# B130.net
KiCad netlist of a schematic drawn in EAGLE
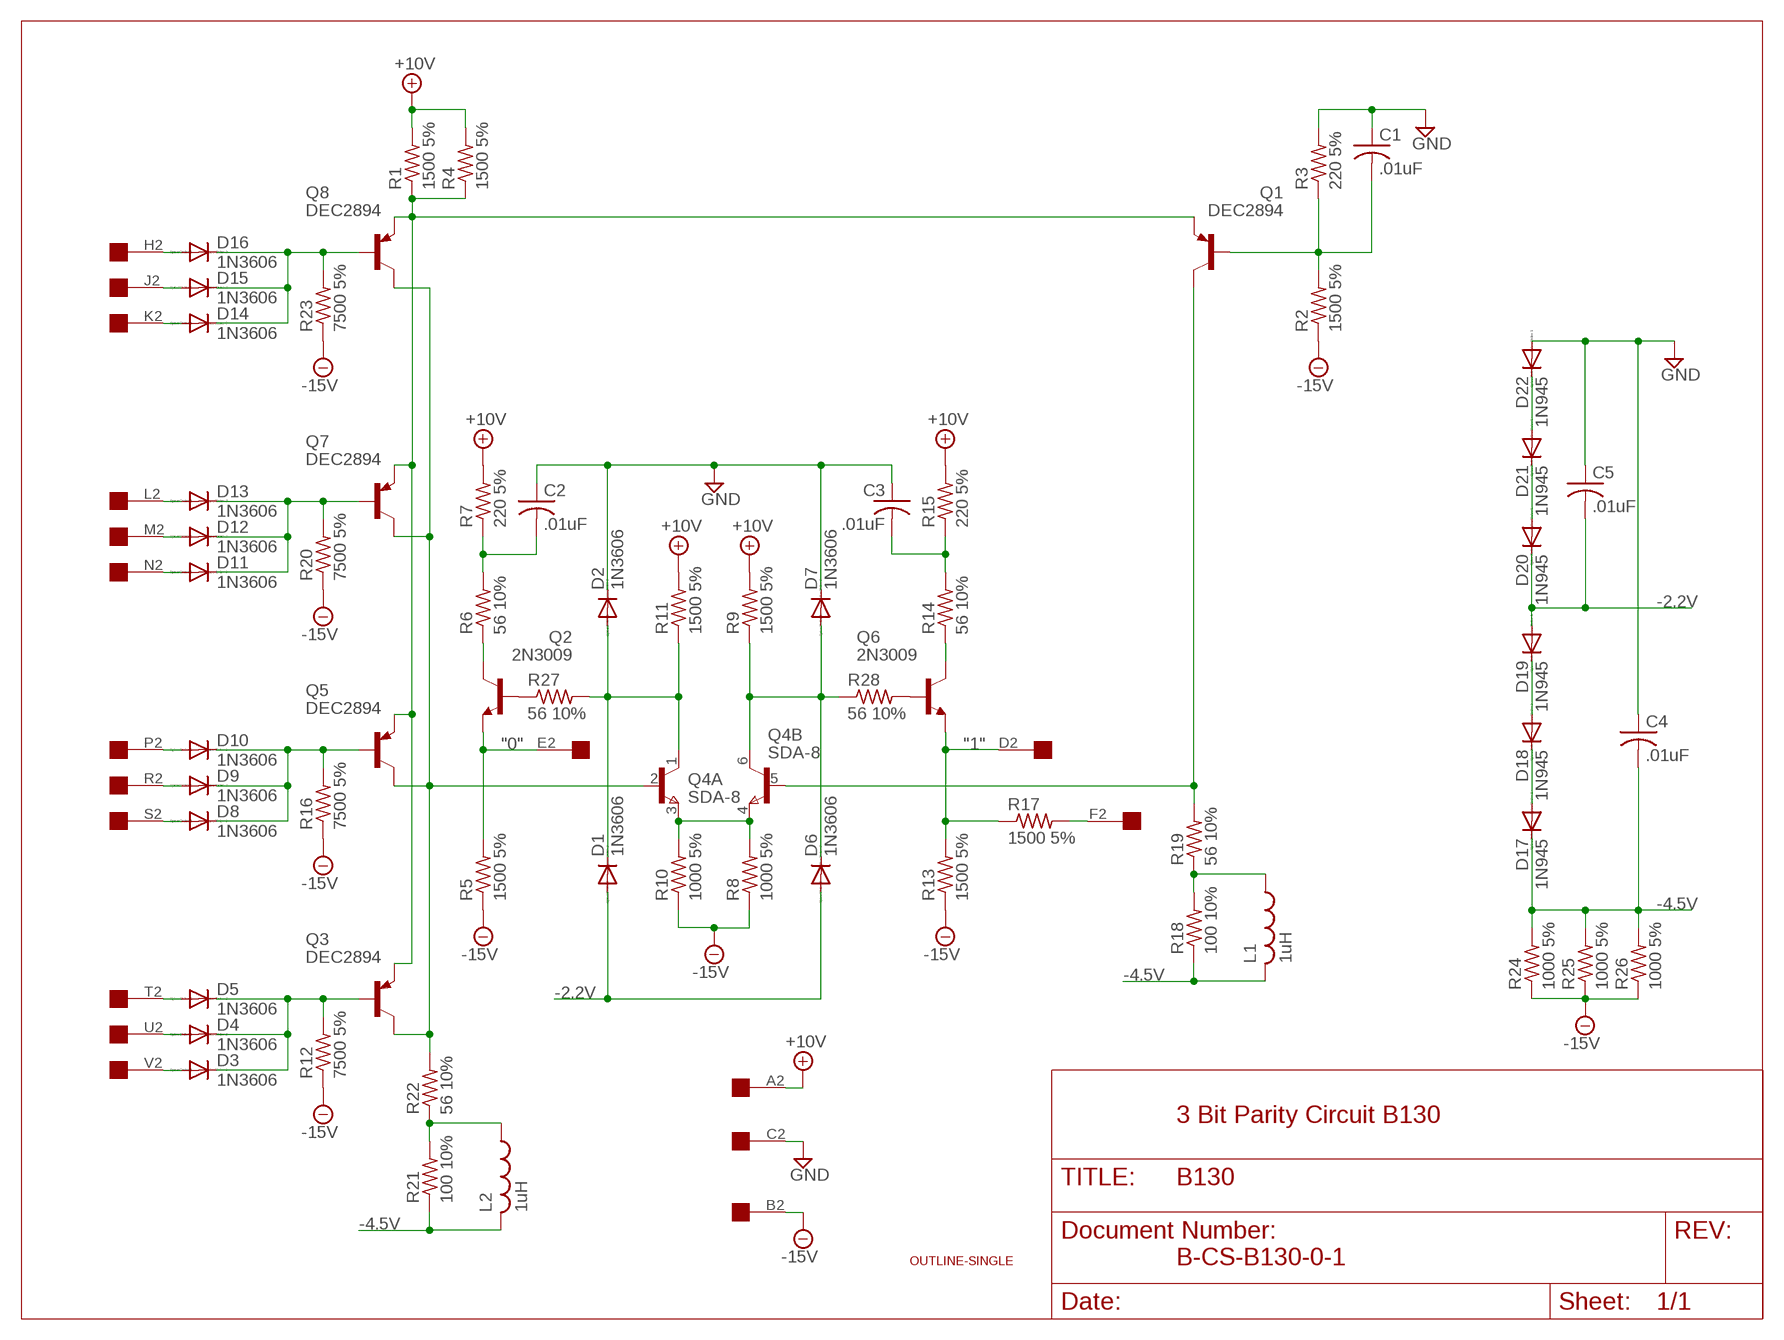
[diagram p0: schematic, sheet 1]

(export (version "E")
  (design (tool "Eeschema 10.0.6"))
  (components
    (comp (ref "C1")
      (value ".01uF")
      (footprint "eagle-import:C050-025X075")
      (libsource (lib "eagle-import") (part "C-US050-025X075"))
    )
    (comp (ref "C2")
      (value ".01uF")
      (footprint "eagle-import:C050-025X075")
      (libsource (lib "eagle-import") (part "C-US050-025X075"))
    )
    (comp (ref "C3")
      (value ".01uF")
      (footprint "eagle-import:C050-025X075")
      (libsource (lib "eagle-import") (part "C-US050-025X075"))
    )
    (comp (ref "C4")
      (value ".01uF")
      (footprint "eagle-import:C050-025X075")
      (libsource (lib "eagle-import") (part "C-US050-025X075"))
    )
    (comp (ref "C5")
      (value ".01uF")
      (footprint "eagle-import:C050-025X075")
      (libsource (lib "eagle-import") (part "C-US050-025X075"))
    )
    (comp (ref "D1")
      (value "1N3606")
      (footprint "eagle-import:DO35-10")
      (libsource (lib "eagle-import") (part "1N4148DO35-10"))
    )
    (comp (ref "D2")
      (value "1N3606")
      (footprint "eagle-import:DO35-10")
      (libsource (lib "eagle-import") (part "1N4148DO35-10"))
    )
    (comp (ref "D3")
      (value "1N3606")
      (footprint "eagle-import:DO35-10")
      (libsource (lib "eagle-import") (part "1N4148DO35-10"))
    )
    (comp (ref "D4")
      (value "1N3606")
      (footprint "eagle-import:DO35-10")
      (libsource (lib "eagle-import") (part "1N4148DO35-10"))
    )
    (comp (ref "D5")
      (value "1N3606")
      (footprint "eagle-import:DO35-10")
      (libsource (lib "eagle-import") (part "1N4148DO35-10"))
    )
    (comp (ref "D6")
      (value "1N3606")
      (footprint "eagle-import:DO35-10")
      (libsource (lib "eagle-import") (part "1N4148DO35-10"))
    )
    (comp (ref "D7")
      (value "1N3606")
      (footprint "eagle-import:DO35-10")
      (libsource (lib "eagle-import") (part "1N4148DO35-10"))
    )
    (comp (ref "D8")
      (value "1N3606")
      (footprint "eagle-import:DO35-10")
      (libsource (lib "eagle-import") (part "1N4148DO35-10"))
    )
    (comp (ref "D9")
      (value "1N3606")
      (footprint "eagle-import:DO35-10")
      (libsource (lib "eagle-import") (part "1N4148DO35-10"))
    )
    (comp (ref "D10")
      (value "1N3606")
      (footprint "eagle-import:DO35-10")
      (libsource (lib "eagle-import") (part "1N4148DO35-10"))
    )
    (comp (ref "D11")
      (value "1N3606")
      (footprint "eagle-import:DO35-10")
      (libsource (lib "eagle-import") (part "1N4148DO35-10"))
    )
    (comp (ref "D12")
      (value "1N3606")
      (footprint "eagle-import:DO35-10")
      (libsource (lib "eagle-import") (part "1N4148DO35-10"))
    )
    (comp (ref "D13")
      (value "1N3606")
      (footprint "eagle-import:DO35-10")
      (libsource (lib "eagle-import") (part "1N4148DO35-10"))
    )
    (comp (ref "D14")
      (value "1N3606")
      (footprint "eagle-import:DO35-10")
      (libsource (lib "eagle-import") (part "1N4148DO35-10"))
    )
    (comp (ref "D15")
      (value "1N3606")
      (footprint "eagle-import:DO35-10")
      (libsource (lib "eagle-import") (part "1N4148DO35-10"))
    )
    (comp (ref "D16")
      (value "1N3606")
      (footprint "eagle-import:DO35-10")
      (libsource (lib "eagle-import") (part "1N4148DO35-10"))
    )
    (comp (ref "D17")
      (value "1N945")
      (footprint "eagle-import:DO35-10")
      (libsource (lib "eagle-import") (part "1N4148DO35-10"))
    )
    (comp (ref "D18")
      (value "1N945")
      (footprint "eagle-import:DO35-10")
      (libsource (lib "eagle-import") (part "1N4148DO35-10"))
    )
    (comp (ref "D19")
      (value "1N945")
      (footprint "eagle-import:DO35-10")
      (libsource (lib "eagle-import") (part "1N4148DO35-10"))
    )
    (comp (ref "D20")
      (value "1N945")
      (footprint "eagle-import:DO35-10")
      (libsource (lib "eagle-import") (part "1N4148DO35-10"))
    )
    (comp (ref "D21")
      (value "1N945")
      (footprint "eagle-import:DO35-10")
      (libsource (lib "eagle-import") (part "1N4148DO35-10"))
    )
    (comp (ref "D22")
      (value "1N945")
      (footprint "eagle-import:DO35-10")
      (libsource (lib "eagle-import") (part "1N4148DO35-10"))
    )
    (comp (ref "L1")
      (value "1uH")
      (footprint "eagle-import:0207_10")
      (libsource (lib "eagle-import") (part "L-US0207/10"))
    )
    (comp (ref "L2")
      (value "1uH")
      (footprint "eagle-import:0207_10")
      (libsource (lib "eagle-import") (part "L-US0207/10"))
    )
    (comp (ref "Q1")
      (value "DEC2894")
      (footprint "eagle-import:TO39")
      (libsource (lib "eagle-import") (part "2N2904"))
    )
    (comp (ref "Q2")
      (value "2N3009")
      (footprint "eagle-import:TO5")
      (libsource (lib "eagle-import") (part "2N2102"))
    )
    (comp (ref "Q3")
      (value "DEC2894")
      (footprint "eagle-import:TO39")
      (libsource (lib "eagle-import") (part "2N2904"))
    )
    (comp (ref "Q4")
      (value "SDA-8")
      (footprint "eagle-import:TO78")
      (libsource (lib "eagle-import") (part "MAT-02H"))
    )
    (comp (ref "Q5")
      (value "DEC2894")
      (footprint "eagle-import:TO39")
      (libsource (lib "eagle-import") (part "2N2904"))
    )
    (comp (ref "Q6")
      (value "2N3009")
      (footprint "eagle-import:TO5")
      (libsource (lib "eagle-import") (part "2N2102"))
    )
    (comp (ref "Q7")
      (value "DEC2894")
      (footprint "eagle-import:TO39")
      (libsource (lib "eagle-import") (part "2N2904"))
    )
    (comp (ref "Q8")
      (value "DEC2894")
      (footprint "eagle-import:TO39")
      (libsource (lib "eagle-import") (part "2N2904"))
    )
    (comp (ref "R1")
      (value "1500 5%")
      (footprint "eagle-import:0207_10")
      (libsource (lib "eagle-import") (part "R-US_0207/10"))
    )
    (comp (ref "R2")
      (value "1500 5%")
      (footprint "eagle-import:0207_10")
      (libsource (lib "eagle-import") (part "R-US_0207/10"))
    )
    (comp (ref "R3")
      (value "220 5%")
      (footprint "eagle-import:0207_10")
      (libsource (lib "eagle-import") (part "R-US_0207/10"))
    )
    (comp (ref "R4")
      (value "1500 5%")
      (footprint "eagle-import:0207_10")
      (libsource (lib "eagle-import") (part "R-US_0207/10"))
    )
    (comp (ref "R5")
      (value "1500 5%")
      (footprint "eagle-import:0207_10")
      (libsource (lib "eagle-import") (part "R-US_0207/10"))
    )
    (comp (ref "R6")
      (value "56 10%")
      (footprint "eagle-import:0207_10")
      (libsource (lib "eagle-import") (part "R-US_0207/10"))
    )
    (comp (ref "R7")
      (value "220 5%")
      (footprint "eagle-import:0207_10")
      (libsource (lib "eagle-import") (part "R-US_0207/10"))
    )
    (comp (ref "R8")
      (value "1000 5%")
      (footprint "eagle-import:0207_10")
      (libsource (lib "eagle-import") (part "R-US_0207/10"))
    )
    (comp (ref "R9")
      (value "1500 5%")
      (footprint "eagle-import:0207_10")
      (libsource (lib "eagle-import") (part "R-US_0207/10"))
    )
    (comp (ref "R10")
      (value "1000 5%")
      (footprint "eagle-import:0207_10")
      (libsource (lib "eagle-import") (part "R-US_0207/10"))
    )
    (comp (ref "R11")
      (value "1500 5%")
      (footprint "eagle-import:0207_10")
      (libsource (lib "eagle-import") (part "R-US_0207/10"))
    )
    (comp (ref "R12")
      (value "7500 5%")
      (footprint "eagle-import:0207_10")
      (libsource (lib "eagle-import") (part "R-US_0207/10"))
    )
    (comp (ref "R13")
      (value "1500 5%")
      (footprint "eagle-import:0207_10")
      (libsource (lib "eagle-import") (part "R-US_0207/10"))
    )
    (comp (ref "R14")
      (value "56 10%")
      (footprint "eagle-import:0207_10")
      (libsource (lib "eagle-import") (part "R-US_0207/10"))
    )
    (comp (ref "R15")
      (value "220 5%")
      (footprint "eagle-import:0207_10")
      (libsource (lib "eagle-import") (part "R-US_0207/10"))
    )
    (comp (ref "R16")
      (value "7500 5%")
      (footprint "eagle-import:0207_10")
      (libsource (lib "eagle-import") (part "R-US_0207/10"))
    )
    (comp (ref "R17")
      (value "1500 5%")
      (footprint "eagle-import:0207_10")
      (libsource (lib "eagle-import") (part "R-US_0207/10"))
    )
    (comp (ref "R18")
      (value "100 10%")
      (footprint "eagle-import:0207_10")
      (libsource (lib "eagle-import") (part "R-US_0207/10"))
    )
    (comp (ref "R19")
      (value "56 10%")
      (footprint "eagle-import:0207_10")
      (libsource (lib "eagle-import") (part "R-US_0207/10"))
    )
    (comp (ref "R20")
      (value "7500 5%")
      (footprint "eagle-import:0207_10")
      (libsource (lib "eagle-import") (part "R-US_0207/10"))
    )
    (comp (ref "R21")
      (value "100 10%")
      (footprint "eagle-import:0207_10")
      (libsource (lib "eagle-import") (part "R-US_0207/10"))
    )
    (comp (ref "R22")
      (value "56 10%")
      (footprint "eagle-import:0207_10")
      (libsource (lib "eagle-import") (part "R-US_0207/10"))
    )
    (comp (ref "R23")
      (value "7500 5%")
      (footprint "eagle-import:0207_10")
      (libsource (lib "eagle-import") (part "R-US_0207/10"))
    )
    (comp (ref "R24")
      (value "1000 5%")
      (footprint "eagle-import:0207_10")
      (libsource (lib "eagle-import") (part "R-US_0207/10"))
    )
    (comp (ref "R25")
      (value "1000 5%")
      (footprint "eagle-import:0207_10")
      (libsource (lib "eagle-import") (part "R-US_0207/10"))
    )
    (comp (ref "R26")
      (value "1000 5%")
      (footprint "eagle-import:0207_10")
      (libsource (lib "eagle-import") (part "R-US_0207/10"))
    )
    (comp (ref "R27")
      (value "56 10%")
      (footprint "eagle-import:0207_10")
      (libsource (lib "eagle-import") (part "R-US_0207/10"))
    )
    (comp (ref "R28")
      (value "56 10%")
      (footprint "eagle-import:0207_10")
      (libsource (lib "eagle-import") (part "R-US_0207/10"))
    )
    (comp (ref "U$1")
      (value "OUTLINE-SINGLE")
      (footprint "eagle-import:SINGLE")
      (libsource (lib "eagle-import") (part "OUTLINE-SINGLE"))
    )
    (comp (ref "U$2")
      (value "EDGE-1")
      (footprint "eagle-import:EDGE-CON1")
      (libsource (lib "eagle-import") (part "EDGE-1"))
    )
  )
  (nets
    (net (code "1") (name "+10V") (class "Default")
      (node (ref "R1") (pin "2") (pinfunction "2_2") (pintype "passive"))
      (node (ref "R11") (pin "2") (pinfunction "2_2") (pintype "passive"))
      (node (ref "R15") (pin "2") (pinfunction "2_2") (pintype "passive"))
      (node (ref "R4") (pin "2") (pinfunction "2_2") (pintype "passive"))
      (node (ref "R7") (pin "2") (pinfunction "2_2") (pintype "passive"))
      (node (ref "R9") (pin "2") (pinfunction "2_2") (pintype "passive"))
      (node (ref "U$2") (pin "A2") (pinfunction "1_A2") (pintype "bidirectional"))
    )
    (net (code "2") (name "-15V") (class "Default")
      (node (ref "R10") (pin "1") (pinfunction "1_1") (pintype "passive"))
      (node (ref "R12") (pin "1") (pinfunction "1_1") (pintype "passive"))
      (node (ref "R13") (pin "1") (pinfunction "1_1") (pintype "passive"))
      (node (ref "R16") (pin "1") (pinfunction "1_1") (pintype "passive"))
      (node (ref "R2") (pin "1") (pinfunction "1_1") (pintype "passive"))
      (node (ref "R20") (pin "1") (pinfunction "1_1") (pintype "passive"))
      (node (ref "R23") (pin "1") (pinfunction "1_1") (pintype "passive"))
      (node (ref "R24") (pin "1") (pinfunction "1_1") (pintype "passive"))
      (node (ref "R25") (pin "1") (pinfunction "1_1") (pintype "passive"))
      (node (ref "R26") (pin "1") (pinfunction "1_1") (pintype "passive"))
      (node (ref "R5") (pin "1") (pinfunction "1_1") (pintype "passive"))
      (node (ref "R8") (pin "1") (pinfunction "1_1") (pintype "passive"))
      (node (ref "U$2") (pin "B2") (pinfunction "1_B2") (pintype "bidirectional"))
    )
    (net (code "3") (name "/\"0\"") (class "Default")
      (node (ref "Q2") (pin "1") (pinfunction "E_1") (pintype "passive"))
      (node (ref "R5") (pin "2") (pinfunction "2_2") (pintype "passive"))
      (node (ref "U$2") (pin "E2") (pinfunction "1_E2") (pintype "bidirectional"))
    )
    (net (code "4") (name "/\"1\"") (class "Default")
      (node (ref "Q6") (pin "1") (pinfunction "E_1") (pintype "passive"))
      (node (ref "R13") (pin "2") (pinfunction "2_2") (pintype "passive"))
      (node (ref "R17") (pin "1") (pinfunction "1_1") (pintype "passive"))
      (node (ref "U$2") (pin "D2") (pinfunction "1_D2") (pintype "bidirectional"))
    )
    (net (code "5") (name "/-2.2V") (class "Default")
      (node (ref "C5") (pin "2") (pinfunction "2_2") (pintype "passive"))
      (node (ref "D1") (pin "A") (pinfunction "A_A") (pintype "passive"))
      (node (ref "D19") (pin "A") (pinfunction "A_A") (pintype "passive"))
      (node (ref "D20") (pin "C") (pinfunction "C_C") (pintype "passive"))
      (node (ref "D6") (pin "A") (pinfunction "A_A") (pintype "passive"))
    )
    (net (code "6") (name "/-4.5V") (class "Default")
      (node (ref "C4") (pin "2") (pinfunction "2_2") (pintype "passive"))
      (node (ref "D17") (pin "C") (pinfunction "C_C") (pintype "passive"))
      (node (ref "L1") (pin "2") (pinfunction "2_2") (pintype "passive"))
      (node (ref "L2") (pin "2") (pinfunction "2_2") (pintype "passive"))
      (node (ref "R18") (pin "1") (pinfunction "1_1") (pintype "passive"))
      (node (ref "R21") (pin "1") (pinfunction "1_1") (pintype "passive"))
      (node (ref "R24") (pin "2") (pinfunction "2_2") (pintype "passive"))
      (node (ref "R25") (pin "2") (pinfunction "2_2") (pintype "passive"))
      (node (ref "R26") (pin "2") (pinfunction "2_2") (pintype "passive"))
    )
    (net (code "7") (name "GND") (class "Default")
      (node (ref "C1") (pin "1") (pinfunction "1_1") (pintype "passive"))
      (node (ref "C2") (pin "1") (pinfunction "1_1") (pintype "passive"))
      (node (ref "C3") (pin "1") (pinfunction "1_1") (pintype "passive"))
      (node (ref "C4") (pin "1") (pinfunction "1_1") (pintype "passive"))
      (node (ref "C5") (pin "1") (pinfunction "1_1") (pintype "passive"))
      (node (ref "D2") (pin "C") (pinfunction "C_C") (pintype "passive"))
      (node (ref "D22") (pin "A") (pinfunction "A_A") (pintype "passive"))
      (node (ref "D7") (pin "C") (pinfunction "C_C") (pintype "passive"))
      (node (ref "R3") (pin "2") (pinfunction "2_2") (pintype "passive"))
      (node (ref "U$2") (pin "C2") (pinfunction "1_C2") (pintype "bidirectional"))
    )
    (net (code "8") (name "Net-(C2-Pad2)") (class "Default")
      (node (ref "C2") (pin "2") (pinfunction "2_2") (pintype "passive"))
      (node (ref "R6") (pin "2") (pinfunction "2_2") (pintype "passive"))
      (node (ref "R7") (pin "1") (pinfunction "1_1") (pintype "passive"))
    )
    (net (code "9") (name "Net-(C3-Pad2)") (class "Default")
      (node (ref "C3") (pin "2") (pinfunction "2_2") (pintype "passive"))
      (node (ref "R14") (pin "2") (pinfunction "2_2") (pintype "passive"))
      (node (ref "R15") (pin "1") (pinfunction "1_1") (pintype "passive"))
    )
    (net (code "10") (name "Net-(D17-PadA)") (class "Default")
      (node (ref "D17") (pin "A") (pinfunction "A_A") (pintype "passive"))
      (node (ref "D18") (pin "C") (pinfunction "C_C") (pintype "passive"))
    )
    (net (code "11") (name "Net-(D18-PadA)") (class "Default")
      (node (ref "D18") (pin "A") (pinfunction "A_A") (pintype "passive"))
      (node (ref "D19") (pin "C") (pinfunction "C_C") (pintype "passive"))
    )
    (net (code "12") (name "Net-(D20-PadA)") (class "Default")
      (node (ref "D20") (pin "A") (pinfunction "A_A") (pintype "passive"))
      (node (ref "D21") (pin "C") (pinfunction "C_C") (pintype "passive"))
    )
    (net (code "13") (name "Net-(D21-PadA)") (class "Default")
      (node (ref "D21") (pin "A") (pinfunction "A_A") (pintype "passive"))
      (node (ref "D22") (pin "C") (pinfunction "C_C") (pintype "passive"))
    )
    (net (code "14") (name "Net-(L1-Pad1)") (class "Default")
      (node (ref "L1") (pin "1") (pinfunction "1_1") (pintype "passive"))
      (node (ref "R18") (pin "2") (pinfunction "2_2") (pintype "passive"))
      (node (ref "R19") (pin "1") (pinfunction "1_1") (pintype "passive"))
    )
    (net (code "15") (name "Net-(L2-Pad1)") (class "Default")
      (node (ref "L2") (pin "1") (pinfunction "1_1") (pintype "passive"))
      (node (ref "R21") (pin "2") (pinfunction "2_2") (pintype "passive"))
      (node (ref "R22") (pin "1") (pinfunction "1_1") (pintype "passive"))
    )
    (net (code "16") (name "Net-(Q1-B)") (class "Default")
      (node (ref "C1") (pin "2") (pinfunction "2_2") (pintype "passive"))
      (node (ref "Q1") (pin "2") (pinfunction "B_2") (pintype "passive"))
      (node (ref "R2") (pin "2") (pinfunction "2_2") (pintype "passive"))
      (node (ref "R3") (pin "1") (pinfunction "1_1") (pintype "passive"))
    )
    (net (code "17") (name "Net-(Q1-C)") (class "Default")
      (node (ref "Q1") (pin "3") (pinfunction "C_3") (pintype "passive"))
      (node (ref "Q4") (pin "5") (pinfunction "B_5") (pintype "passive"))
      (node (ref "R19") (pin "2") (pinfunction "2_2") (pintype "passive"))
    )
    (net (code "18") (name "Net-(Q1-E)") (class "Default")
      (node (ref "Q1") (pin "1") (pinfunction "E_1") (pintype "passive"))
      (node (ref "Q3") (pin "1") (pinfunction "E_1") (pintype "passive"))
      (node (ref "Q5") (pin "1") (pinfunction "E_1") (pintype "passive"))
      (node (ref "Q7") (pin "1") (pinfunction "E_1") (pintype "passive"))
      (node (ref "Q8") (pin "1") (pinfunction "E_1") (pintype "passive"))
      (node (ref "R1") (pin "1") (pinfunction "1_1") (pintype "passive"))
      (node (ref "R4") (pin "1") (pinfunction "1_1") (pintype "passive"))
    )
    (net (code "19") (name "Net-(Q2-B)") (class "Default")
      (node (ref "Q2") (pin "2") (pinfunction "B_2") (pintype "passive"))
      (node (ref "R27") (pin "1") (pinfunction "1_1") (pintype "passive"))
    )
    (net (code "20") (name "Net-(Q2-C)") (class "Default")
      (node (ref "Q2") (pin "3") (pinfunction "C_3") (pintype "passive"))
      (node (ref "R6") (pin "1") (pinfunction "1_1") (pintype "passive"))
    )
    (net (code "21") (name "Net-(Q3-B)") (class "Default")
      (node (ref "D3") (pin "C") (pinfunction "C_C") (pintype "passive"))
      (node (ref "D4") (pin "C") (pinfunction "C_C") (pintype "passive"))
      (node (ref "D5") (pin "C") (pinfunction "C_C") (pintype "passive"))
      (node (ref "Q3") (pin "2") (pinfunction "B_2") (pintype "passive"))
      (node (ref "R12") (pin "2") (pinfunction "2_2") (pintype "passive"))
    )
    (net (code "22") (name "Net-(Q3-C)") (class "Default")
      (node (ref "Q3") (pin "3") (pinfunction "C_3") (pintype "passive"))
      (node (ref "Q4") (pin "2") (pinfunction "B_2") (pintype "passive"))
      (node (ref "Q5") (pin "3") (pinfunction "C_3") (pintype "passive"))
      (node (ref "Q7") (pin "3") (pinfunction "C_3") (pintype "passive"))
      (node (ref "Q8") (pin "3") (pinfunction "C_3") (pintype "passive"))
      (node (ref "R22") (pin "2") (pinfunction "2_2") (pintype "passive"))
    )
    (net (code "23") (name "Net-(Q4A-C)") (class "Default")
      (node (ref "D1") (pin "C") (pinfunction "C_C") (pintype "passive"))
      (node (ref "D2") (pin "A") (pinfunction "A_A") (pintype "passive"))
      (node (ref "Q4") (pin "1") (pinfunction "C_1") (pintype "passive"))
      (node (ref "R11") (pin "1") (pinfunction "1_1") (pintype "passive"))
      (node (ref "R27") (pin "2") (pinfunction "2_2") (pintype "passive"))
    )
    (net (code "24") (name "Net-(Q4A-E)") (class "Default")
      (node (ref "Q4") (pin "3") (pinfunction "E_3") (pintype "passive"))
      (node (ref "Q4") (pin "4") (pinfunction "E_4") (pintype "passive"))
      (node (ref "R10") (pin "2") (pinfunction "2_2") (pintype "passive"))
      (node (ref "R8") (pin "2") (pinfunction "2_2") (pintype "passive"))
    )
    (net (code "25") (name "Net-(Q4B-C)") (class "Default")
      (node (ref "D6") (pin "C") (pinfunction "C_C") (pintype "passive"))
      (node (ref "D7") (pin "A") (pinfunction "A_A") (pintype "passive"))
      (node (ref "Q4") (pin "6") (pinfunction "C_6") (pintype "passive"))
      (node (ref "R28") (pin "1") (pinfunction "1_1") (pintype "passive"))
      (node (ref "R9") (pin "1") (pinfunction "1_1") (pintype "passive"))
    )
    (net (code "26") (name "Net-(Q5-B)") (class "Default")
      (node (ref "D10") (pin "C") (pinfunction "C_C") (pintype "passive"))
      (node (ref "D8") (pin "C") (pinfunction "C_C") (pintype "passive"))
      (node (ref "D9") (pin "C") (pinfunction "C_C") (pintype "passive"))
      (node (ref "Q5") (pin "2") (pinfunction "B_2") (pintype "passive"))
      (node (ref "R16") (pin "2") (pinfunction "2_2") (pintype "passive"))
    )
    (net (code "27") (name "Net-(Q6-B)") (class "Default")
      (node (ref "Q6") (pin "2") (pinfunction "B_2") (pintype "passive"))
      (node (ref "R28") (pin "2") (pinfunction "2_2") (pintype "passive"))
    )
    (net (code "28") (name "Net-(Q6-C)") (class "Default")
      (node (ref "Q6") (pin "3") (pinfunction "C_3") (pintype "passive"))
      (node (ref "R14") (pin "1") (pinfunction "1_1") (pintype "passive"))
    )
    (net (code "29") (name "Net-(Q7-B)") (class "Default")
      (node (ref "D11") (pin "C") (pinfunction "C_C") (pintype "passive"))
      (node (ref "D12") (pin "C") (pinfunction "C_C") (pintype "passive"))
      (node (ref "D13") (pin "C") (pinfunction "C_C") (pintype "passive"))
      (node (ref "Q7") (pin "2") (pinfunction "B_2") (pintype "passive"))
      (node (ref "R20") (pin "2") (pinfunction "2_2") (pintype "passive"))
    )
    (net (code "30") (name "Net-(Q8-B)") (class "Default")
      (node (ref "D14") (pin "C") (pinfunction "C_C") (pintype "passive"))
      (node (ref "D15") (pin "C") (pinfunction "C_C") (pintype "passive"))
      (node (ref "D16") (pin "C") (pinfunction "C_C") (pintype "passive"))
      (node (ref "Q8") (pin "2") (pinfunction "B_2") (pintype "passive"))
      (node (ref "R23") (pin "2") (pinfunction "2_2") (pintype "passive"))
    )
    (net (code "31") (name "Net-(U$2F-1)") (class "Default")
      (node (ref "R17") (pin "2") (pinfunction "2_2") (pintype "passive"))
      (node (ref "U$2") (pin "F2") (pinfunction "1_F2") (pintype "bidirectional"))
    )
    (net (code "32") (name "Net-(U$2G-1)") (class "Default")
      (node (ref "D16") (pin "A") (pinfunction "A_A") (pintype "passive"))
      (node (ref "U$2") (pin "H2") (pinfunction "1_H2") (pintype "bidirectional"))
    )
    (net (code "33") (name "Net-(U$2H-1)") (class "Default")
      (node (ref "D15") (pin "A") (pinfunction "A_A") (pintype "passive"))
      (node (ref "U$2") (pin "J2") (pinfunction "1_J2") (pintype "bidirectional"))
    )
    (net (code "34") (name "Net-(U$2I-1)") (class "Default")
      (node (ref "D14") (pin "A") (pinfunction "A_A") (pintype "passive"))
      (node (ref "U$2") (pin "K2") (pinfunction "1_K2") (pintype "bidirectional"))
    )
    (net (code "35") (name "Net-(U$2J-1)") (class "Default")
      (node (ref "D13") (pin "A") (pinfunction "A_A") (pintype "passive"))
      (node (ref "U$2") (pin "L2") (pinfunction "1_L2") (pintype "bidirectional"))
    )
    (net (code "36") (name "Net-(U$2K-1)") (class "Default")
      (node (ref "D12") (pin "A") (pinfunction "A_A") (pintype "passive"))
      (node (ref "U$2") (pin "M2") (pinfunction "1_M2") (pintype "bidirectional"))
    )
    (net (code "37") (name "Net-(U$2L-1)") (class "Default")
      (node (ref "D11") (pin "A") (pinfunction "A_A") (pintype "passive"))
      (node (ref "U$2") (pin "N2") (pinfunction "1_N2") (pintype "bidirectional"))
    )
    (net (code "38") (name "Net-(U$2M-1)") (class "Default")
      (node (ref "D10") (pin "A") (pinfunction "A_A") (pintype "passive"))
      (node (ref "U$2") (pin "P2") (pinfunction "1_P2") (pintype "bidirectional"))
    )
    (net (code "39") (name "Net-(U$2N-1)") (class "Default")
      (node (ref "D9") (pin "A") (pinfunction "A_A") (pintype "passive"))
      (node (ref "U$2") (pin "R2") (pinfunction "1_R2") (pintype "bidirectional"))
    )
    (net (code "40") (name "Net-(U$2O-1)") (class "Default")
      (node (ref "D8") (pin "A") (pinfunction "A_A") (pintype "passive"))
      (node (ref "U$2") (pin "S2") (pinfunction "1_S2") (pintype "bidirectional"))
    )
    (net (code "41") (name "Net-(U$2P-1)") (class "Default")
      (node (ref "D5") (pin "A") (pinfunction "A_A") (pintype "passive"))
      (node (ref "U$2") (pin "T2") (pinfunction "1_T2") (pintype "bidirectional"))
    )
    (net (code "42") (name "Net-(U$2Q-1)") (class "Default")
      (node (ref "D4") (pin "A") (pinfunction "A_A") (pintype "passive"))
      (node (ref "U$2") (pin "U2") (pinfunction "1_U2") (pintype "bidirectional"))
    )
    (net (code "43") (name "Net-(U$2R-1)") (class "Default")
      (node (ref "D3") (pin "A") (pinfunction "A_A") (pintype "passive"))
      (node (ref "U$2") (pin "V2") (pinfunction "1_V2") (pintype "bidirectional"))
    )
  )
)
